# NewMUM.net
KiCad netlist of a schematic drawn in EAGLE
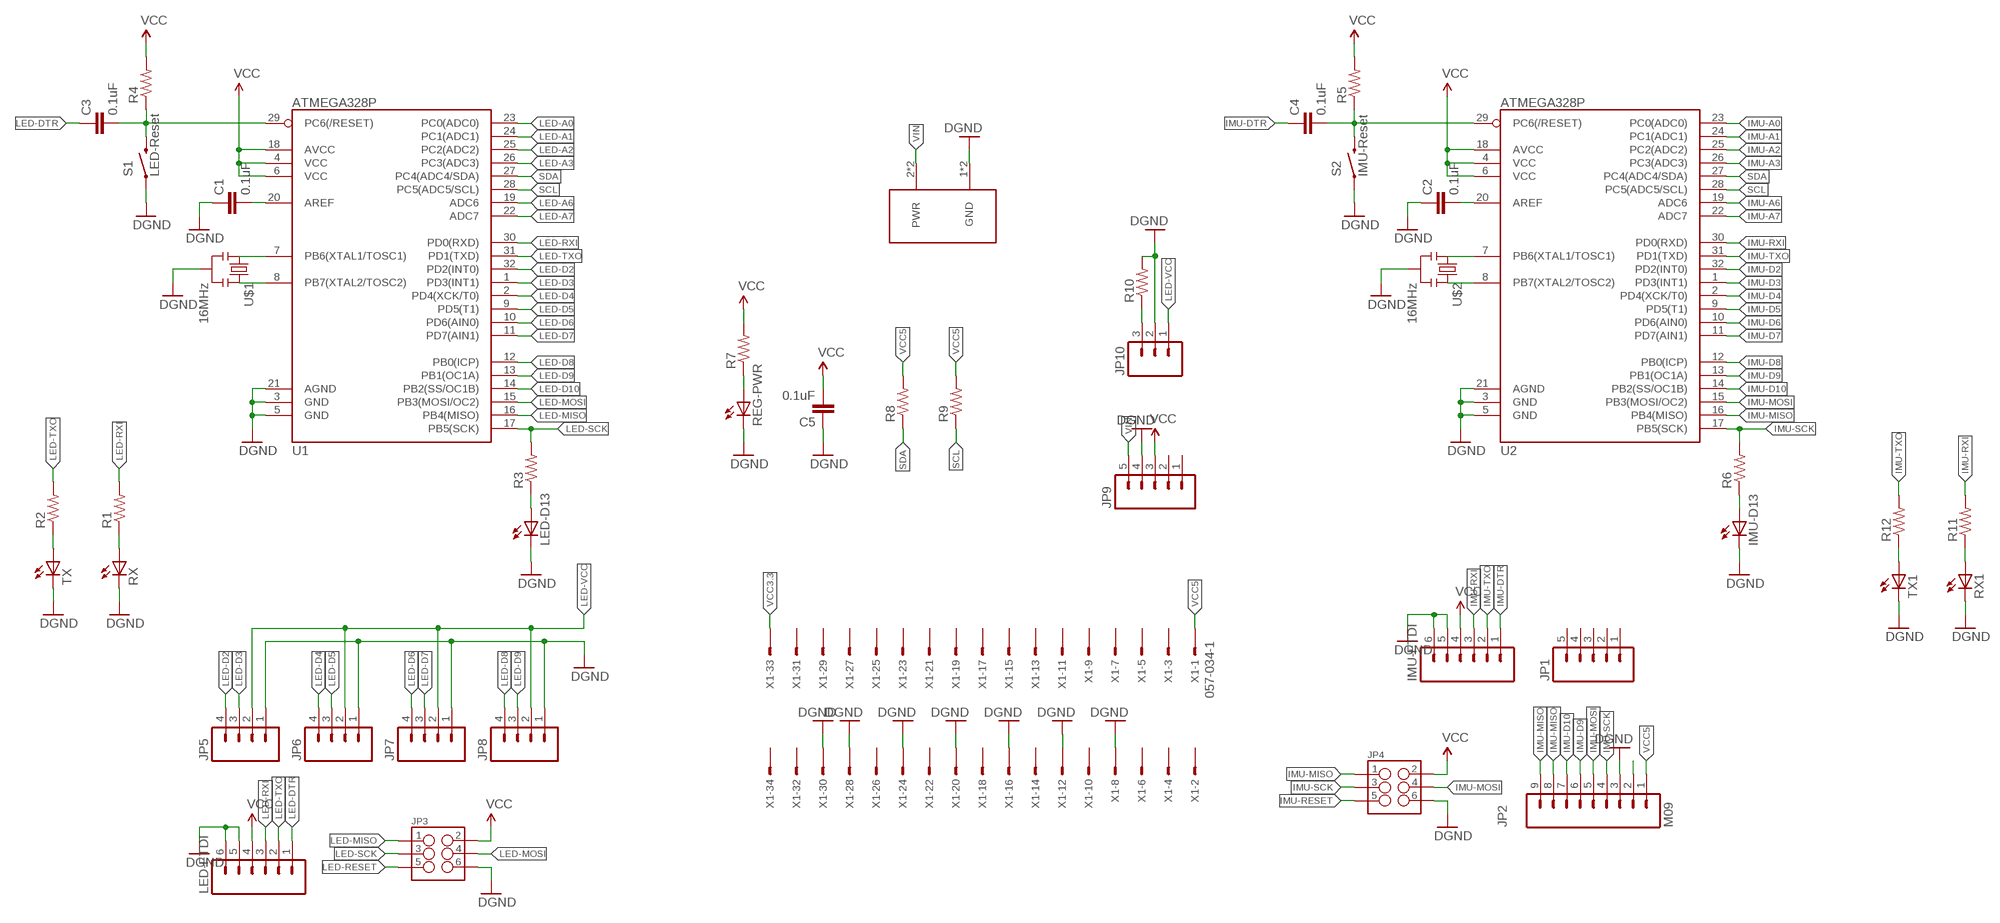
[diagram p0: schematic, sheet 1]

(export (version "E")
  (design (tool "Eeschema 10.0.6"))
  (components
    (comp (ref "C1")
      (value "0.1uF")
      (footprint "eagle-import:0805")
      (libsource (lib "eagle-import") (part "CAP0805"))
    )
    (comp (ref "C2")
      (value "0.1uF")
      (footprint "eagle-import:0805")
      (libsource (lib "eagle-import") (part "CAP0805"))
    )
    (comp (ref "C3")
      (value "0.1uF")
      (footprint "eagle-import:0805")
      (libsource (lib "eagle-import") (part "CAP0805"))
    )
    (comp (ref "C4")
      (value "0.1uF")
      (footprint "eagle-import:0805")
      (libsource (lib "eagle-import") (part "CAP0805"))
    )
    (comp (ref "C5")
      (value "0.1uF")
      (footprint "eagle-import:0805")
      (libsource (lib "eagle-import") (part "CAP0805"))
    )
    (comp (ref "IMU-D13")
      (value "LED1206")
      (footprint "eagle-import:LED-1206")
      (libsource (lib "eagle-import") (part "LED1206"))
    )
    (comp (ref "IMU-FTDI")
      (value "M06SIP")
      (footprint "eagle-import:1X06")
      (libsource (lib "eagle-import") (part "M06SIP"))
    )
    (comp (ref "JP1")
      (value "M05PTH")
      (footprint "eagle-import:1X05")
      (libsource (lib "eagle-import") (part "M05PTH"))
    )
    (comp (ref "JP2")
      (value "M09")
      (footprint "eagle-import:1X09")
      (libsource (lib "eagle-import") (part "M09"))
    )
    (comp (ref "JP3")
      (value "M03X22X3_SILK_SM")
      (footprint "eagle-import:2X3")
      (libsource (lib "eagle-import") (part "M03X22X3_SILK_SM"))
    )
    (comp (ref "JP4")
      (value "M03X22X3_SILK_SM")
      (footprint "eagle-import:2X3")
      (libsource (lib "eagle-import") (part "M03X22X3_SILK_SM"))
    )
    (comp (ref "JP5")
      (value "M04PTH")
      (footprint "eagle-import:1X04")
      (libsource (lib "eagle-import") (part "M04PTH"))
    )
    (comp (ref "JP6")
      (value "M04PTH")
      (footprint "eagle-import:1X04")
      (libsource (lib "eagle-import") (part "M04PTH"))
    )
    (comp (ref "JP7")
      (value "M04PTH")
      (footprint "eagle-import:1X04")
      (libsource (lib "eagle-import") (part "M04PTH"))
    )
    (comp (ref "JP8")
      (value "M04PTH")
      (footprint "eagle-import:1X04")
      (libsource (lib "eagle-import") (part "M04PTH"))
    )
    (comp (ref "JP9")
      (value "M05PTH")
      (footprint "eagle-import:1X05")
      (libsource (lib "eagle-import") (part "M05PTH"))
    )
    (comp (ref "JP10")
      (value "M03PTH")
      (footprint "eagle-import:1X03")
      (libsource (lib "eagle-import") (part "M03PTH"))
    )
    (comp (ref "LED-D13")
      (value "LED1206")
      (footprint "eagle-import:LED-1206")
      (libsource (lib "eagle-import") (part "LED1206"))
    )
    (comp (ref "LED-FTDI")
      (value "M06SIP")
      (footprint "eagle-import:1X06")
      (libsource (lib "eagle-import") (part "M06SIP"))
    )
    (comp (ref "R1")
      (value "RESISTOR0805-RES")
      (footprint "eagle-import:0805")
      (libsource (lib "eagle-import") (part "RESISTOR0805-RES"))
    )
    (comp (ref "R2")
      (value "RESISTOR0805-RES")
      (footprint "eagle-import:0805")
      (libsource (lib "eagle-import") (part "RESISTOR0805-RES"))
    )
    (comp (ref "R3")
      (value "RESISTOR0805-RES")
      (footprint "eagle-import:0805")
      (libsource (lib "eagle-import") (part "RESISTOR0805-RES"))
    )
    (comp (ref "R4")
      (value "RESISTOR0805-RES")
      (footprint "eagle-import:0805")
      (libsource (lib "eagle-import") (part "RESISTOR0805-RES"))
    )
    (comp (ref "R5")
      (value "RESISTOR0805-RES")
      (footprint "eagle-import:0805")
      (libsource (lib "eagle-import") (part "RESISTOR0805-RES"))
    )
    (comp (ref "R6")
      (value "RESISTOR0805-RES")
      (footprint "eagle-import:0805")
      (libsource (lib "eagle-import") (part "RESISTOR0805-RES"))
    )
    (comp (ref "R7")
      (value "RESISTOR0805-RES")
      (footprint "eagle-import:0805")
      (libsource (lib "eagle-import") (part "RESISTOR0805-RES"))
    )
    (comp (ref "R8")
      (value "RESISTOR0805-RES")
      (footprint "eagle-import:0805")
      (libsource (lib "eagle-import") (part "RESISTOR0805-RES"))
    )
    (comp (ref "R9")
      (value "RESISTOR0805-RES")
      (footprint "eagle-import:0805")
      (libsource (lib "eagle-import") (part "RESISTOR0805-RES"))
    )
    (comp (ref "R10")
      (value "RESISTOR0805-RES")
      (footprint "eagle-import:0805")
      (libsource (lib "eagle-import") (part "RESISTOR0805-RES"))
    )
    (comp (ref "R11")
      (value "RESISTOR0805-RES")
      (footprint "eagle-import:0805")
      (libsource (lib "eagle-import") (part "RESISTOR0805-RES"))
    )
    (comp (ref "R12")
      (value "RESISTOR0805-RES")
      (footprint "eagle-import:0805")
      (libsource (lib "eagle-import") (part "RESISTOR0805-RES"))
    )
    (comp (ref "REG-PWR")
      (value "LED1206")
      (footprint "eagle-import:LED-1206")
      (libsource (lib "eagle-import") (part "LED1206"))
    )
    (comp (ref "RX")
      (value "LED1206")
      (footprint "eagle-import:LED-1206")
      (libsource (lib "eagle-import") (part "LED1206"))
    )
    (comp (ref "RX1")
      (value "LED1206")
      (footprint "eagle-import:LED-1206")
      (libsource (lib "eagle-import") (part "LED1206"))
    )
    (comp (ref "S1")
      (value "LED-Reset")
      (footprint "eagle-import:TACTILE-PTH")
      (libsource (lib "eagle-import") (part "SWITCH-MOMENTARY-2PTH"))
    )
    (comp (ref "S2")
      (value "IMU-Reset")
      (footprint "eagle-import:TACTILE-PTH")
      (libsource (lib "eagle-import") (part "SWITCH-MOMENTARY-2PTH"))
    )
    (comp (ref "TX")
      (value "LED1206")
      (footprint "eagle-import:LED-1206")
      (libsource (lib "eagle-import") (part "LED1206"))
    )
    (comp (ref "TX1")
      (value "LED1206")
      (footprint "eagle-import:LED-1206")
      (libsource (lib "eagle-import") (part "LED1206"))
    )
    (comp (ref "U$1")
      (value "16MHz")
      (footprint "eagle-import:RESONATOR-WIDE-SMD")
      (libsource (lib "eagle-import") (part "RESONATOR-WIDE"))
    )
    (comp (ref "U$2")
      (value "16MHz")
      (footprint "eagle-import:RESONATOR-WIDE-SMD")
      (libsource (lib "eagle-import") (part "RESONATOR-WIDE"))
    )
    (comp (ref "U$3")
      (value "LSF-SMT")
      (footprint "eagle-import:LSF-SMT")
      (libsource (lib "eagle-import") (part "LSF-SMT"))
    )
    (comp (ref "U1")
      (value "ATMEGA328P")
      (footprint "eagle-import:TQFP32-08")
      (libsource (lib "eagle-import") (part "ATMEGA328_SMT"))
    )
    (comp (ref "U2")
      (value "ATMEGA328P")
      (footprint "eagle-import:TQFP32-08")
      (libsource (lib "eagle-import") (part "ATMEGA328_SMT"))
    )
    (comp (ref "X1")
      (value "057-034-1")
      (footprint "eagle-import:057-034-1")
      (libsource (lib "eagle-import") (part "057-034-1"))
    )
  )
  (nets
    (net (code "1") (name "DGND") (class "Default")
      (node (ref "C1") (pin "1") (pinfunction "1_1") (pintype "passive"))
      (node (ref "C2") (pin "1") (pinfunction "1_1") (pintype "passive"))
      (node (ref "C5") (pin "1") (pinfunction "1_1") (pintype "passive"))
      (node (ref "IMU-D13") (pin "C") (pinfunction "C_C") (pintype "passive"))
      (node (ref "IMU-FTDI") (pin "5") (pinfunction "5_5") (pintype "passive"))
      (node (ref "IMU-FTDI") (pin "6") (pinfunction "6_6") (pintype "passive"))
      (node (ref "JP10") (pin "2") (pinfunction "2_2") (pintype "passive"))
      (node (ref "JP2") (pin "3") (pinfunction "3_3") (pintype "passive"))
      (node (ref "JP3") (pin "6") (pinfunction "6_6") (pintype "bidirectional"))
      (node (ref "JP4") (pin "6") (pinfunction "6_6") (pintype "bidirectional"))
      (node (ref "JP5") (pin "1") (pinfunction "1_1") (pintype "passive"))
      (node (ref "JP6") (pin "1") (pinfunction "1_1") (pintype "passive"))
      (node (ref "JP7") (pin "1") (pinfunction "1_1") (pintype "passive"))
      (node (ref "JP8") (pin "1") (pinfunction "1_1") (pintype "passive"))
      (node (ref "JP9") (pin "4") (pinfunction "4_4") (pintype "passive"))
      (node (ref "LED-D13") (pin "C") (pinfunction "C_C") (pintype "passive"))
      (node (ref "LED-FTDI") (pin "5") (pinfunction "5_5") (pintype "passive"))
      (node (ref "LED-FTDI") (pin "6") (pinfunction "6_6") (pintype "passive"))
      (node (ref "R10") (pin "2") (pinfunction "2_2") (pintype "passive"))
      (node (ref "REG-PWR") (pin "C") (pinfunction "C_C") (pintype "passive"))
      (node (ref "RX") (pin "C") (pinfunction "C_C") (pintype "passive"))
      (node (ref "RX1") (pin "C") (pinfunction "C_C") (pintype "passive"))
      (node (ref "S1") (pin "1") (pinfunction "1_1") (pintype "passive"))
      (node (ref "S2") (pin "1") (pinfunction "1_1") (pintype "passive"))
      (node (ref "TX") (pin "C") (pinfunction "C_C") (pintype "passive"))
      (node (ref "TX1") (pin "C") (pinfunction "C_C") (pintype "passive"))
      (node (ref "U$1") (pin "2") (pinfunction "2_2") (pintype "passive"))
      (node (ref "U$2") (pin "2") (pinfunction "2_2") (pintype "passive"))
      (node (ref "U$3") (pin "1") (pinfunction "GND_1") (pintype "bidirectional"))
      (node (ref "U$3") (pin "1-2") (pinfunction "GND_1-2") (pintype "bidirectional"))
      (node (ref "U1") (pin "21") (pinfunction "AGND_21") (pintype "bidirectional"))
      (node (ref "U1") (pin "3") (pinfunction "GND_3") (pintype "bidirectional"))
      (node (ref "U1") (pin "5") (pinfunction "GND_5") (pintype "bidirectional"))
      (node (ref "U2") (pin "21") (pinfunction "AGND_21") (pintype "bidirectional"))
      (node (ref "U2") (pin "3") (pinfunction "GND_3") (pintype "bidirectional"))
      (node (ref "U2") (pin "5") (pinfunction "GND_5") (pintype "bidirectional"))
      (node (ref "X1") (pin "12") (pinfunction "S_12") (pintype "passive"))
      (node (ref "X1") (pin "16") (pinfunction "S_16") (pintype "passive"))
      (node (ref "X1") (pin "20") (pinfunction "S_20") (pintype "passive"))
      (node (ref "X1") (pin "24") (pinfunction "S_24") (pintype "passive"))
      (node (ref "X1") (pin "28") (pinfunction "S_28") (pintype "passive"))
      (node (ref "X1") (pin "30") (pinfunction "S_30") (pintype "passive"))
      (node (ref "X1") (pin "8") (pinfunction "S_8") (pintype "passive"))
    )
    (net (code "2") (name "IMU-A0") (class "Default")
      (node (ref "U2") (pin "23") (pinfunction "PC0(ADC0)_23") (pintype "bidirectional"))
    )
    (net (code "3") (name "IMU-A1") (class "Default")
      (node (ref "U2") (pin "24") (pinfunction "PC1(ADC1)_24") (pintype "bidirectional"))
    )
    (net (code "4") (name "IMU-A2") (class "Default")
      (node (ref "U2") (pin "25") (pinfunction "PC2(ADC2)_25") (pintype "bidirectional"))
    )
    (net (code "5") (name "IMU-A3") (class "Default")
      (node (ref "U2") (pin "26") (pinfunction "PC3(ADC3)_26") (pintype "bidirectional"))
    )
    (net (code "6") (name "IMU-A6") (class "Default")
      (node (ref "U2") (pin "19") (pinfunction "ADC6_19") (pintype "bidirectional"))
    )
    (net (code "7") (name "IMU-A7") (class "Default")
      (node (ref "U2") (pin "22") (pinfunction "ADC7_22") (pintype "bidirectional"))
    )
    (net (code "8") (name "IMU-D2") (class "Default")
      (node (ref "U2") (pin "32") (pinfunction "PD2(INT0)_32") (pintype "bidirectional"))
    )
    (net (code "9") (name "IMU-D3") (class "Default")
      (node (ref "U2") (pin "1") (pinfunction "PD3(INT1)_1") (pintype "bidirectional"))
    )
    (net (code "10") (name "IMU-D4") (class "Default")
      (node (ref "U2") (pin "2") (pinfunction "PD4(XCK/T0)_2") (pintype "bidirectional"))
    )
    (net (code "11") (name "IMU-D5") (class "Default")
      (node (ref "U2") (pin "9") (pinfunction "PD5(T1)_9") (pintype "bidirectional"))
    )
    (net (code "12") (name "IMU-D6") (class "Default")
      (node (ref "U2") (pin "10") (pinfunction "PD6(AIN0)_10") (pintype "bidirectional"))
    )
    (net (code "13") (name "IMU-D7") (class "Default")
      (node (ref "U2") (pin "11") (pinfunction "PD7(AIN1)_11") (pintype "bidirectional"))
    )
    (net (code "14") (name "IMU-D8") (class "Default")
      (node (ref "U2") (pin "12") (pinfunction "PB0(ICP)_12") (pintype "bidirectional"))
    )
    (net (code "15") (name "IMU-D9") (class "Default")
      (node (ref "JP2") (pin "6") (pinfunction "6_6") (pintype "passive"))
      (node (ref "U2") (pin "13") (pinfunction "PB1(OC1A)_13") (pintype "bidirectional"))
    )
    (net (code "16") (name "IMU-D10") (class "Default")
      (node (ref "JP2") (pin "7") (pinfunction "7_7") (pintype "passive"))
      (node (ref "U2") (pin "14") (pinfunction "PB2(SS/OC1B)_14") (pintype "bidirectional"))
    )
    (net (code "17") (name "IMU-DTR") (class "Default")
      (node (ref "C4") (pin "1") (pinfunction "1_1") (pintype "passive"))
      (node (ref "IMU-FTDI") (pin "1") (pinfunction "1_1") (pintype "passive"))
    )
    (net (code "18") (name "IMU-MISO") (class "Default")
      (node (ref "JP2") (pin "8") (pinfunction "8_8") (pintype "passive"))
      (node (ref "JP2") (pin "9") (pinfunction "9_9") (pintype "passive"))
      (node (ref "JP4") (pin "1") (pinfunction "1_1") (pintype "bidirectional"))
      (node (ref "U2") (pin "16") (pinfunction "PB4(MISO)_16") (pintype "bidirectional"))
    )
    (net (code "19") (name "IMU-MOSI") (class "Default")
      (node (ref "JP2") (pin "5") (pinfunction "5_5") (pintype "passive"))
      (node (ref "JP4") (pin "4") (pinfunction "4_4") (pintype "bidirectional"))
      (node (ref "U2") (pin "15") (pinfunction "PB3(MOSI/OC2)_15") (pintype "bidirectional"))
    )
    (net (code "20") (name "IMU-RESET") (class "Default")
      (node (ref "C4") (pin "2") (pinfunction "2_2") (pintype "passive"))
      (node (ref "JP4") (pin "5") (pinfunction "5_5") (pintype "bidirectional"))
      (node (ref "R5") (pin "1") (pinfunction "1_1") (pintype "passive"))
      (node (ref "S2") (pin "3") (pinfunction "2_3") (pintype "passive"))
      (node (ref "U2") (pin "29") (pinfunction "PC6(/RESET)_29") (pintype "bidirectional"))
    )
    (net (code "21") (name "IMU-RXI") (class "Default")
      (node (ref "IMU-FTDI") (pin "3") (pinfunction "3_3") (pintype "passive"))
      (node (ref "R11") (pin "2") (pinfunction "2_2") (pintype "passive"))
      (node (ref "U2") (pin "30") (pinfunction "PD0(RXD)_30") (pintype "bidirectional"))
    )
    (net (code "22") (name "IMU-SCK") (class "Default")
      (node (ref "JP2") (pin "4") (pinfunction "4_4") (pintype "passive"))
      (node (ref "JP4") (pin "3") (pinfunction "3_3") (pintype "bidirectional"))
      (node (ref "R6") (pin "2") (pinfunction "2_2") (pintype "passive"))
      (node (ref "U2") (pin "17") (pinfunction "PB5(SCK)_17") (pintype "bidirectional"))
    )
    (net (code "23") (name "IMU-TXO") (class "Default")
      (node (ref "IMU-FTDI") (pin "2") (pinfunction "2_2") (pintype "passive"))
      (node (ref "R12") (pin "2") (pinfunction "2_2") (pintype "passive"))
      (node (ref "U2") (pin "31") (pinfunction "PD1(TXD)_31") (pintype "bidirectional"))
    )
    (net (code "24") (name "LED-A0") (class "Default")
      (node (ref "U1") (pin "23") (pinfunction "PC0(ADC0)_23") (pintype "bidirectional"))
    )
    (net (code "25") (name "LED-A1") (class "Default")
      (node (ref "U1") (pin "24") (pinfunction "PC1(ADC1)_24") (pintype "bidirectional"))
    )
    (net (code "26") (name "LED-A2") (class "Default")
      (node (ref "U1") (pin "25") (pinfunction "PC2(ADC2)_25") (pintype "bidirectional"))
    )
    (net (code "27") (name "LED-A3") (class "Default")
      (node (ref "U1") (pin "26") (pinfunction "PC3(ADC3)_26") (pintype "bidirectional"))
    )
    (net (code "28") (name "LED-A6") (class "Default")
      (node (ref "U1") (pin "19") (pinfunction "ADC6_19") (pintype "bidirectional"))
    )
    (net (code "29") (name "LED-A7") (class "Default")
      (node (ref "U1") (pin "22") (pinfunction "ADC7_22") (pintype "bidirectional"))
    )
    (net (code "30") (name "LED-D2") (class "Default")
      (node (ref "JP5") (pin "4") (pinfunction "4_4") (pintype "passive"))
      (node (ref "U1") (pin "32") (pinfunction "PD2(INT0)_32") (pintype "bidirectional"))
    )
    (net (code "31") (name "LED-D3") (class "Default")
      (node (ref "JP5") (pin "3") (pinfunction "3_3") (pintype "passive"))
      (node (ref "U1") (pin "1") (pinfunction "PD3(INT1)_1") (pintype "bidirectional"))
    )
    (net (code "32") (name "LED-D4") (class "Default")
      (node (ref "JP6") (pin "4") (pinfunction "4_4") (pintype "passive"))
      (node (ref "U1") (pin "2") (pinfunction "PD4(XCK/T0)_2") (pintype "bidirectional"))
    )
    (net (code "33") (name "LED-D5") (class "Default")
      (node (ref "JP6") (pin "3") (pinfunction "3_3") (pintype "passive"))
      (node (ref "U1") (pin "9") (pinfunction "PD5(T1)_9") (pintype "bidirectional"))
    )
    (net (code "34") (name "LED-D6") (class "Default")
      (node (ref "JP7") (pin "4") (pinfunction "4_4") (pintype "passive"))
      (node (ref "U1") (pin "10") (pinfunction "PD6(AIN0)_10") (pintype "bidirectional"))
    )
    (net (code "35") (name "LED-D7") (class "Default")
      (node (ref "JP7") (pin "3") (pinfunction "3_3") (pintype "passive"))
      (node (ref "U1") (pin "11") (pinfunction "PD7(AIN1)_11") (pintype "bidirectional"))
    )
    (net (code "36") (name "LED-D8") (class "Default")
      (node (ref "JP8") (pin "4") (pinfunction "4_4") (pintype "passive"))
      (node (ref "U1") (pin "12") (pinfunction "PB0(ICP)_12") (pintype "bidirectional"))
    )
    (net (code "37") (name "LED-D9") (class "Default")
      (node (ref "JP8") (pin "3") (pinfunction "3_3") (pintype "passive"))
      (node (ref "U1") (pin "13") (pinfunction "PB1(OC1A)_13") (pintype "bidirectional"))
    )
    (net (code "38") (name "LED-D10") (class "Default")
      (node (ref "U1") (pin "14") (pinfunction "PB2(SS/OC1B)_14") (pintype "bidirectional"))
    )
    (net (code "39") (name "LED-DTR") (class "Default")
      (node (ref "C3") (pin "1") (pinfunction "1_1") (pintype "passive"))
      (node (ref "LED-FTDI") (pin "1") (pinfunction "1_1") (pintype "passive"))
    )
    (net (code "40") (name "LED-MISO") (class "Default")
      (node (ref "JP3") (pin "1") (pinfunction "1_1") (pintype "bidirectional"))
      (node (ref "U1") (pin "16") (pinfunction "PB4(MISO)_16") (pintype "bidirectional"))
    )
    (net (code "41") (name "LED-MOSI") (class "Default")
      (node (ref "JP3") (pin "4") (pinfunction "4_4") (pintype "bidirectional"))
      (node (ref "U1") (pin "15") (pinfunction "PB3(MOSI/OC2)_15") (pintype "bidirectional"))
    )
    (net (code "42") (name "LED-RESET") (class "Default")
      (node (ref "C3") (pin "2") (pinfunction "2_2") (pintype "passive"))
      (node (ref "JP3") (pin "5") (pinfunction "5_5") (pintype "bidirectional"))
      (node (ref "R4") (pin "1") (pinfunction "1_1") (pintype "passive"))
      (node (ref "S1") (pin "3") (pinfunction "2_3") (pintype "passive"))
      (node (ref "U1") (pin "29") (pinfunction "PC6(/RESET)_29") (pintype "bidirectional"))
    )
    (net (code "43") (name "LED-RXI") (class "Default")
      (node (ref "LED-FTDI") (pin "3") (pinfunction "3_3") (pintype "passive"))
      (node (ref "R1") (pin "2") (pinfunction "2_2") (pintype "passive"))
      (node (ref "U1") (pin "30") (pinfunction "PD0(RXD)_30") (pintype "bidirectional"))
    )
    (net (code "44") (name "LED-SCK") (class "Default")
      (node (ref "JP3") (pin "3") (pinfunction "3_3") (pintype "bidirectional"))
      (node (ref "R3") (pin "2") (pinfunction "2_2") (pintype "passive"))
      (node (ref "U1") (pin "17") (pinfunction "PB5(SCK)_17") (pintype "bidirectional"))
    )
    (net (code "45") (name "LED-TXO") (class "Default")
      (node (ref "LED-FTDI") (pin "2") (pinfunction "2_2") (pintype "passive"))
      (node (ref "R2") (pin "2") (pinfunction "2_2") (pintype "passive"))
      (node (ref "U1") (pin "31") (pinfunction "PD1(TXD)_31") (pintype "bidirectional"))
    )
    (net (code "46") (name "LED-VCC") (class "Default")
      (node (ref "JP10") (pin "1") (pinfunction "1_1") (pintype "passive"))
      (node (ref "JP5") (pin "2") (pinfunction "2_2") (pintype "passive"))
      (node (ref "JP6") (pin "2") (pinfunction "2_2") (pintype "passive"))
      (node (ref "JP7") (pin "2") (pinfunction "2_2") (pintype "passive"))
      (node (ref "JP8") (pin "2") (pinfunction "2_2") (pintype "passive"))
    )
    (net (code "47") (name "Net-(IMU-D13-PadA)") (class "Default")
      (node (ref "IMU-D13") (pin "A") (pinfunction "A_A") (pintype "passive"))
      (node (ref "R6") (pin "1") (pinfunction "1_1") (pintype "passive"))
    )
    (net (code "48") (name "Net-(JP10-Pad3)") (class "Default")
      (node (ref "JP10") (pin "3") (pinfunction "3_3") (pintype "passive"))
      (node (ref "R10") (pin "1") (pinfunction "1_1") (pintype "passive"))
    )
    (net (code "49") (name "Net-(LED-D13-PadA)") (class "Default")
      (node (ref "LED-D13") (pin "A") (pinfunction "A_A") (pintype "passive"))
      (node (ref "R3") (pin "1") (pinfunction "1_1") (pintype "passive"))
    )
    (net (code "50") (name "Net-(R1-Pad1)") (class "Default")
      (node (ref "R1") (pin "1") (pinfunction "1_1") (pintype "passive"))
      (node (ref "RX") (pin "A") (pinfunction "A_A") (pintype "passive"))
    )
    (net (code "51") (name "Net-(R2-Pad1)") (class "Default")
      (node (ref "R2") (pin "1") (pinfunction "1_1") (pintype "passive"))
      (node (ref "TX") (pin "A") (pinfunction "A_A") (pintype "passive"))
    )
    (net (code "52") (name "Net-(R7-Pad1)") (class "Default")
      (node (ref "R7") (pin "1") (pinfunction "1_1") (pintype "passive"))
      (node (ref "REG-PWR") (pin "A") (pinfunction "A_A") (pintype "passive"))
    )
    (net (code "53") (name "Net-(R11-Pad1)") (class "Default")
      (node (ref "R11") (pin "1") (pinfunction "1_1") (pintype "passive"))
      (node (ref "RX1") (pin "A") (pinfunction "A_A") (pintype "passive"))
    )
    (net (code "54") (name "Net-(R12-Pad1)") (class "Default")
      (node (ref "R12") (pin "1") (pinfunction "1_1") (pintype "passive"))
      (node (ref "TX1") (pin "A") (pinfunction "A_A") (pintype "passive"))
    )
    (net (code "55") (name "Net-(U1-AREF)") (class "Default")
      (node (ref "C1") (pin "2") (pinfunction "2_2") (pintype "passive"))
      (node (ref "U1") (pin "20") (pinfunction "AREF_20") (pintype "bidirectional"))
    )
    (net (code "56") (name "Net-(U1-PB6(XTAL1{slash}TOSC1))") (class "Default")
      (node (ref "U$1") (pin "1") (pinfunction "1_1") (pintype "passive"))
      (node (ref "U1") (pin "7") (pinfunction "PB6(XTAL1/TOSC1)_7") (pintype "bidirectional"))
    )
    (net (code "57") (name "Net-(U1-PB7(XTAL2{slash}TOSC2))") (class "Default")
      (node (ref "U$1") (pin "3") (pinfunction "3_3") (pintype "passive"))
      (node (ref "U1") (pin "8") (pinfunction "PB7(XTAL2/TOSC2)_8") (pintype "bidirectional"))
    )
    (net (code "58") (name "Net-(U2-AREF)") (class "Default")
      (node (ref "C2") (pin "2") (pinfunction "2_2") (pintype "passive"))
      (node (ref "U2") (pin "20") (pinfunction "AREF_20") (pintype "bidirectional"))
    )
    (net (code "59") (name "Net-(U2-PB6(XTAL1{slash}TOSC1))") (class "Default")
      (node (ref "U$2") (pin "1") (pinfunction "1_1") (pintype "passive"))
      (node (ref "U2") (pin "7") (pinfunction "PB6(XTAL1/TOSC1)_7") (pintype "bidirectional"))
    )
    (net (code "60") (name "Net-(U2-PB7(XTAL2{slash}TOSC2))") (class "Default")
      (node (ref "U$2") (pin "3") (pinfunction "3_3") (pintype "passive"))
      (node (ref "U2") (pin "8") (pinfunction "PB7(XTAL2/TOSC2)_8") (pintype "bidirectional"))
    )
    (net (code "61") (name "SCL") (class "Default")
      (node (ref "R9") (pin "1") (pinfunction "1_1") (pintype "passive"))
      (node (ref "U1") (pin "28") (pinfunction "PC5(ADC5/SCL)_28") (pintype "bidirectional"))
      (node (ref "U2") (pin "28") (pinfunction "PC5(ADC5/SCL)_28") (pintype "bidirectional"))
    )
    (net (code "62") (name "SDA") (class "Default")
      (node (ref "R8") (pin "1") (pinfunction "1_1") (pintype "passive"))
      (node (ref "U1") (pin "27") (pinfunction "PC4(ADC4/SDA)_27") (pintype "bidirectional"))
      (node (ref "U2") (pin "27") (pinfunction "PC4(ADC4/SDA)_27") (pintype "bidirectional"))
    )
    (net (code "63") (name "VCC") (class "Default")
      (node (ref "C5") (pin "2") (pinfunction "2_2") (pintype "passive"))
      (node (ref "IMU-FTDI") (pin "4") (pinfunction "4_4") (pintype "passive"))
      (node (ref "JP3") (pin "2") (pinfunction "2_2") (pintype "bidirectional"))
      (node (ref "JP4") (pin "2") (pinfunction "2_2") (pintype "bidirectional"))
      (node (ref "JP9") (pin "3") (pinfunction "3_3") (pintype "passive"))
      (node (ref "LED-FTDI") (pin "4") (pinfunction "4_4") (pintype "passive"))
      (node (ref "R4") (pin "2") (pinfunction "2_2") (pintype "passive"))
      (node (ref "R5") (pin "2") (pinfunction "2_2") (pintype "passive"))
      (node (ref "R7") (pin "2") (pinfunction "2_2") (pintype "passive"))
      (node (ref "U1") (pin "18") (pinfunction "AVCC_18") (pintype "bidirectional"))
      (node (ref "U1") (pin "4") (pinfunction "VCC_4") (pintype "bidirectional"))
      (node (ref "U1") (pin "6") (pinfunction "VCC_6") (pintype "bidirectional"))
      (node (ref "U2") (pin "18") (pinfunction "AVCC_18") (pintype "bidirectional"))
      (node (ref "U2") (pin "4") (pinfunction "VCC_4") (pintype "bidirectional"))
      (node (ref "U2") (pin "6") (pinfunction "VCC_6") (pintype "bidirectional"))
    )
    (net (code "64") (name "VCC3.3") (class "Default")
      (node (ref "X1") (pin "33") (pinfunction "S_33") (pintype "passive"))
    )
    (net (code "65") (name "VCC5") (class "Default")
      (node (ref "JP2") (pin "1") (pinfunction "1_1") (pintype "passive"))
      (node (ref "R8") (pin "2") (pinfunction "2_2") (pintype "passive"))
      (node (ref "R9") (pin "2") (pinfunction "2_2") (pintype "passive"))
      (node (ref "X1") (pin "1") (pinfunction "S_1") (pintype "passive"))
    )
    (net (code "66") (name "VIN") (class "Default")
      (node (ref "JP9") (pin "5") (pinfunction "5_5") (pintype "passive"))
      (node (ref "U$3") (pin "2") (pinfunction "PWR_2") (pintype "bidirectional"))
      (node (ref "U$3") (pin "2-2") (pinfunction "PWR_2-2") (pintype "bidirectional"))
    )
    (net (code "67") (name "unconnected-(JP1-Pad1)") (class "Default")
      (node (ref "JP1") (pin "1") (pinfunction "1_1") (pintype "passive"))
    )
    (net (code "68") (name "unconnected-(JP1-Pad2)") (class "Default")
      (node (ref "JP1") (pin "2") (pinfunction "2_2") (pintype "passive"))
    )
    (net (code "69") (name "unconnected-(JP1-Pad3)") (class "Default")
      (node (ref "JP1") (pin "3") (pinfunction "3_3") (pintype "passive"))
    )
    (net (code "70") (name "unconnected-(JP1-Pad4)") (class "Default")
      (node (ref "JP1") (pin "4") (pinfunction "4_4") (pintype "passive"))
    )
    (net (code "71") (name "unconnected-(JP1-Pad5)") (class "Default")
      (node (ref "JP1") (pin "5") (pinfunction "5_5") (pintype "passive"))
    )
    (net (code "72") (name "unconnected-(JP2-Pad2)") (class "Default")
      (node (ref "JP2") (pin "2") (pinfunction "2_2") (pintype "passive"))
    )
    (net (code "73") (name "unconnected-(JP9-Pad1)") (class "Default")
      (node (ref "JP9") (pin "1") (pinfunction "1_1") (pintype "passive"))
    )
    (net (code "74") (name "unconnected-(JP9-Pad2)") (class "Default")
      (node (ref "JP9") (pin "2") (pinfunction "2_2") (pintype "passive"))
    )
    (net (code "75") (name "unconnected-(X1AB-S-Pad34)") (class "Default")
      (node (ref "X1") (pin "34") (pinfunction "S_34") (pintype "passive"))
    )
    (net (code "76") (name "unconnected-(X1AC-S-Pad4)") (class "Default")
      (node (ref "X1") (pin "4") (pinfunction "S_4") (pintype "passive"))
    )
    (net (code "77") (name "unconnected-(X1AD-S-Pad5)") (class "Default")
      (node (ref "X1") (pin "5") (pinfunction "S_5") (pintype "passive"))
    )
    (net (code "78") (name "unconnected-(X1AE-S-Pad6)") (class "Default")
      (node (ref "X1") (pin "6") (pinfunction "S_6") (pintype "passive"))
    )
    (net (code "79") (name "unconnected-(X1AF-S-Pad7)") (class "Default")
      (node (ref "X1") (pin "7") (pinfunction "S_7") (pintype "passive"))
    )
    (net (code "80") (name "unconnected-(X1AH-S-Pad9)") (class "Default")
      (node (ref "X1") (pin "9") (pinfunction "S_9") (pintype "passive"))
    )
    (net (code "81") (name "unconnected-(X1B-S-Pad10)") (class "Default")
      (node (ref "X1") (pin "10") (pinfunction "S_10") (pintype "passive"))
    )
    (net (code "82") (name "unconnected-(X1C-S-Pad11)") (class "Default")
      (node (ref "X1") (pin "11") (pinfunction "S_11") (pintype "passive"))
    )
    (net (code "83") (name "unconnected-(X1E-S-Pad13)") (class "Default")
      (node (ref "X1") (pin "13") (pinfunction "S_13") (pintype "passive"))
    )
    (net (code "84") (name "unconnected-(X1F-S-Pad14)") (class "Default")
      (node (ref "X1") (pin "14") (pinfunction "S_14") (pintype "passive"))
    )
    (net (code "85") (name "unconnected-(X1G-S-Pad15)") (class "Default")
      (node (ref "X1") (pin "15") (pinfunction "S_15") (pintype "passive"))
    )
    (net (code "86") (name "unconnected-(X1I-S-Pad17)") (class "Default")
      (node (ref "X1") (pin "17") (pinfunction "S_17") (pintype "passive"))
    )
    (net (code "87") (name "unconnected-(X1J-S-Pad18)") (class "Default")
      (node (ref "X1") (pin "18") (pinfunction "S_18") (pintype "passive"))
    )
    (net (code "88") (name "unconnected-(X1K-S-Pad19)") (class "Default")
      (node (ref "X1") (pin "19") (pinfunction "S_19") (pintype "passive"))
    )
    (net (code "89") (name "unconnected-(X1L-S-Pad2)") (class "Default")
      (node (ref "X1") (pin "2") (pinfunction "S_2") (pintype "passive"))
    )
    (net (code "90") (name "unconnected-(X1N-S-Pad21)") (class "Default")
      (node (ref "X1") (pin "21") (pinfunction "S_21") (pintype "passive"))
    )
    (net (code "91") (name "unconnected-(X1O-S-Pad22)") (class "Default")
      (node (ref "X1") (pin "22") (pinfunction "S_22") (pintype "passive"))
    )
    (net (code "92") (name "unconnected-(X1P-S-Pad23)") (class "Default")
      (node (ref "X1") (pin "23") (pinfunction "S_23") (pintype "passive"))
    )
    (net (code "93") (name "unconnected-(X1R-S-Pad25)") (class "Default")
      (node (ref "X1") (pin "25") (pinfunction "S_25") (pintype "passive"))
    )
    (net (code "94") (name "unconnected-(X1S-S-Pad26)") (class "Default")
      (node (ref "X1") (pin "26") (pinfunction "S_26") (pintype "passive"))
    )
    (net (code "95") (name "unconnected-(X1T-S-Pad27)") (class "Default")
      (node (ref "X1") (pin "27") (pinfunction "S_27") (pintype "passive"))
    )
    (net (code "96") (name "unconnected-(X1V-S-Pad29)") (class "Default")
      (node (ref "X1") (pin "29") (pinfunction "S_29") (pintype "passive"))
    )
    (net (code "97") (name "unconnected-(X1W-S-Pad3)") (class "Default")
      (node (ref "X1") (pin "3") (pinfunction "S_3") (pintype "passive"))
    )
    (net (code "98") (name "unconnected-(X1Y-S-Pad31)") (class "Default")
      (node (ref "X1") (pin "31") (pinfunction "S_31") (pintype "passive"))
    )
    (net (code "99") (name "unconnected-(X1Z-S-Pad32)") (class "Default")
      (node (ref "X1") (pin "32") (pinfunction "S_32") (pintype "passive"))
    )
  )
)
